# sumo1.net
KiCad netlist of a schematic drawn in EAGLE
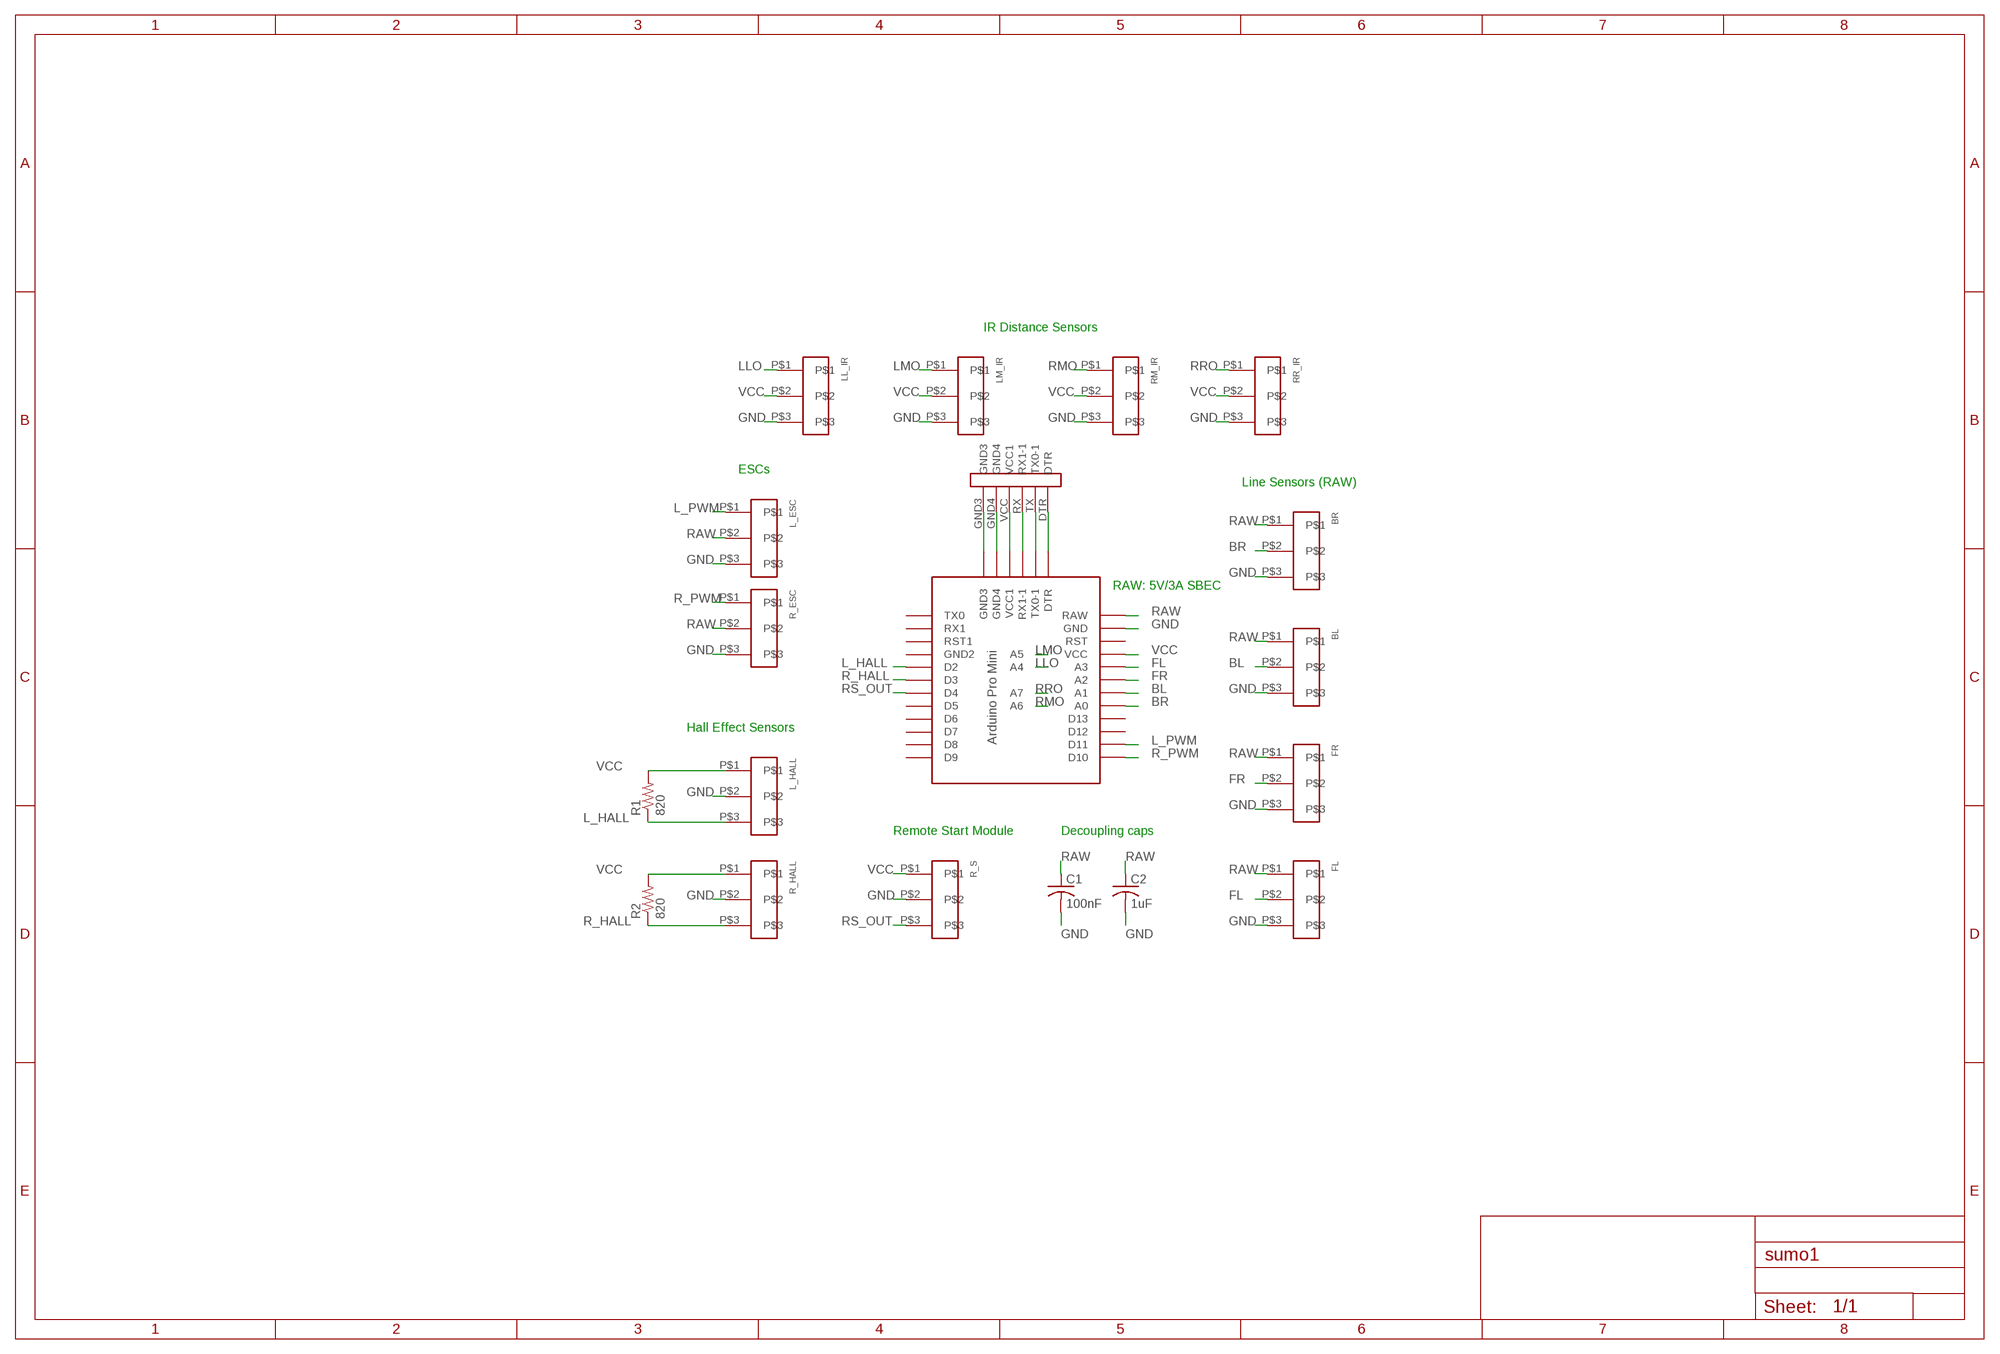
[diagram p0: schematic, sheet 1]

(export (version "E")
  (design (tool "Eeschema 10.0.6"))
  (components
    (comp (ref "BL")
      (value "PHOENIX_CONTACT_3PIN")
      (footprint "eagle-import:PHOENIX_CONTACT_3PIN")
      (libsource (lib "eagle-import") (part "PHOENIX_CONTACT_3PIN"))
    )
    (comp (ref "BR")
      (value "PHOENIX_CONTACT_3PIN")
      (footprint "eagle-import:PHOENIX_CONTACT_3PIN")
      (libsource (lib "eagle-import") (part "PHOENIX_CONTACT_3PIN"))
    )
    (comp (ref "C1")
      (value "100nF")
      (footprint "eagle-import:C0603")
      (libsource (lib "eagle-import") (part "C-USC0603"))
    )
    (comp (ref "C2")
      (value "1uF")
      (footprint "eagle-import:C0603")
      (libsource (lib "eagle-import") (part "C-USC0603"))
    )
    (comp (ref "FL")
      (value "PHOENIX_CONTACT_3PIN")
      (footprint "eagle-import:PHOENIX_CONTACT_3PIN")
      (libsource (lib "eagle-import") (part "PHOENIX_CONTACT_3PIN"))
    )
    (comp (ref "FR")
      (value "PHOENIX_CONTACT_3PIN")
      (footprint "eagle-import:PHOENIX_CONTACT_3PIN")
      (libsource (lib "eagle-import") (part "PHOENIX_CONTACT_3PIN"))
    )
    (comp (ref "LL_IR")
      (value "PHOENIX_CONTACT_3PIN")
      (footprint "eagle-import:PHOENIX_CONTACT_3PIN")
      (libsource (lib "eagle-import") (part "PHOENIX_CONTACT_3PIN"))
    )
    (comp (ref "LM_IR")
      (value "PHOENIX_CONTACT_3PIN")
      (footprint "eagle-import:PHOENIX_CONTACT_3PIN")
      (libsource (lib "eagle-import") (part "PHOENIX_CONTACT_3PIN"))
    )
    (comp (ref "L_ESC")
      (value "PHOENIX_CONTACT_3PIN")
      (footprint "eagle-import:PHOENIX_CONTACT_3PIN")
      (libsource (lib "eagle-import") (part "PHOENIX_CONTACT_3PIN"))
    )
    (comp (ref "L_HALL")
      (value "PHOENIX_CONTACT_3PIN")
      (footprint "eagle-import:PHOENIX_CONTACT_3PIN")
      (libsource (lib "eagle-import") (part "PHOENIX_CONTACT_3PIN"))
    )
    (comp (ref "R1")
      (value "820")
      (footprint "eagle-import:R0603")
      (libsource (lib "eagle-import") (part "R-US_R0603"))
    )
    (comp (ref "R2")
      (value "820")
      (footprint "eagle-import:R0603")
      (libsource (lib "eagle-import") (part "R-US_R0603"))
    )
    (comp (ref "RM_IR")
      (value "PHOENIX_CONTACT_3PIN")
      (footprint "eagle-import:PHOENIX_CONTACT_3PIN")
      (libsource (lib "eagle-import") (part "PHOENIX_CONTACT_3PIN"))
    )
    (comp (ref "RR_IR")
      (value "PHOENIX_CONTACT_3PIN")
      (footprint "eagle-import:PHOENIX_CONTACT_3PIN")
      (libsource (lib "eagle-import") (part "PHOENIX_CONTACT_3PIN"))
    )
    (comp (ref "R_ESC")
      (value "PHOENIX_CONTACT_3PIN")
      (footprint "eagle-import:PHOENIX_CONTACT_3PIN")
      (libsource (lib "eagle-import") (part "PHOENIX_CONTACT_3PIN"))
    )
    (comp (ref "R_HALL")
      (value "PHOENIX_CONTACT_3PIN")
      (footprint "eagle-import:PHOENIX_CONTACT_3PIN")
      (libsource (lib "eagle-import") (part "PHOENIX_CONTACT_3PIN"))
    )
    (comp (ref "R_S")
      (value "PHOENIX_CONTACT_3PIN")
      (footprint "eagle-import:PHOENIX_CONTACT_3PIN")
      (libsource (lib "eagle-import") (part "PHOENIX_CONTACT_3PIN"))
    )
    (comp (ref "U$1")
      (value "PRO-MINI-2")
      (footprint "eagle-import:PRO-MINI-2")
      (libsource (lib "eagle-import") (part "PRO-MINI-2"))
    )
    (comp (ref "U$2")
      (value "6-PIN")
      (footprint "eagle-import:6-PIN")
      (libsource (lib "eagle-import") (part "6-PIN"))
    )
  )
  (nets
    (net (code "1") (name "/BL") (class "Default")
      (node (ref "BL") (pin "P$2") (pinfunction "P$2_P$2") (pintype "bidirectional"))
      (node (ref "U$1") (pin "A1") (pinfunction "A1_A1") (pintype "bidirectional"))
    )
    (net (code "2") (name "/BR") (class "Default")
      (node (ref "BR") (pin "P$2") (pinfunction "P$2_P$2") (pintype "bidirectional"))
      (node (ref "U$1") (pin "A0") (pinfunction "A0_A0") (pintype "bidirectional"))
    )
    (net (code "3") (name "/FL") (class "Default")
      (node (ref "FL") (pin "P$2") (pinfunction "P$2_P$2") (pintype "bidirectional"))
      (node (ref "U$1") (pin "A3") (pinfunction "A3_A3") (pintype "bidirectional"))
    )
    (net (code "4") (name "/FR") (class "Default")
      (node (ref "FR") (pin "P$2") (pinfunction "P$2_P$2") (pintype "bidirectional"))
      (node (ref "U$1") (pin "A2") (pinfunction "A2_A2") (pintype "bidirectional"))
    )
    (net (code "5") (name "/GND") (class "Default")
      (node (ref "BL") (pin "P$3") (pinfunction "P$3_P$3") (pintype "bidirectional"))
      (node (ref "BR") (pin "P$3") (pinfunction "P$3_P$3") (pintype "bidirectional"))
      (node (ref "C1") (pin "2") (pinfunction "2_2") (pintype "passive"))
      (node (ref "C2") (pin "2") (pinfunction "2_2") (pintype "passive"))
      (node (ref "FL") (pin "P$3") (pinfunction "P$3_P$3") (pintype "bidirectional"))
      (node (ref "FR") (pin "P$3") (pinfunction "P$3_P$3") (pintype "bidirectional"))
      (node (ref "LL_IR") (pin "P$3") (pinfunction "P$3_P$3") (pintype "bidirectional"))
      (node (ref "LM_IR") (pin "P$3") (pinfunction "P$3_P$3") (pintype "bidirectional"))
      (node (ref "L_ESC") (pin "P$3") (pinfunction "P$3_P$3") (pintype "bidirectional"))
      (node (ref "L_HALL") (pin "P$2") (pinfunction "P$2_P$2") (pintype "bidirectional"))
      (node (ref "RM_IR") (pin "P$3") (pinfunction "P$3_P$3") (pintype "bidirectional"))
      (node (ref "RR_IR") (pin "P$3") (pinfunction "P$3_P$3") (pintype "bidirectional"))
      (node (ref "R_ESC") (pin "P$3") (pinfunction "P$3_P$3") (pintype "bidirectional"))
      (node (ref "R_HALL") (pin "P$2") (pinfunction "P$2_P$2") (pintype "bidirectional"))
      (node (ref "R_S") (pin "P$2") (pinfunction "P$2_P$2") (pintype "bidirectional"))
      (node (ref "U$1") (pin "GND") (pinfunction "GND_GND") (pintype "bidirectional"))
    )
    (net (code "6") (name "/LLO") (class "Default")
      (node (ref "LL_IR") (pin "P$1") (pinfunction "P$1_P$1") (pintype "bidirectional"))
      (node (ref "U$1") (pin "A4") (pinfunction "A4_A4") (pintype "bidirectional"))
    )
    (net (code "7") (name "/LMO") (class "Default")
      (node (ref "LM_IR") (pin "P$1") (pinfunction "P$1_P$1") (pintype "bidirectional"))
      (node (ref "U$1") (pin "A5") (pinfunction "A5_A5") (pintype "bidirectional"))
    )
    (net (code "8") (name "/L_HALL") (class "Default")
      (node (ref "L_HALL") (pin "P$3") (pinfunction "P$3_P$3") (pintype "bidirectional"))
      (node (ref "R1") (pin "1") (pinfunction "1_1") (pintype "passive"))
      (node (ref "U$1") (pin "D2") (pinfunction "D2_D2") (pintype "bidirectional"))
    )
    (net (code "9") (name "/L_PWM") (class "Default")
      (node (ref "L_ESC") (pin "P$1") (pinfunction "P$1_P$1") (pintype "bidirectional"))
      (node (ref "U$1") (pin "D11") (pinfunction "D11_D11") (pintype "bidirectional"))
    )
    (net (code "10") (name "/RAW") (class "Default")
      (node (ref "BL") (pin "P$1") (pinfunction "P$1_P$1") (pintype "bidirectional"))
      (node (ref "BR") (pin "P$1") (pinfunction "P$1_P$1") (pintype "bidirectional"))
      (node (ref "C1") (pin "1") (pinfunction "1_1") (pintype "passive"))
      (node (ref "C2") (pin "1") (pinfunction "1_1") (pintype "passive"))
      (node (ref "FL") (pin "P$1") (pinfunction "P$1_P$1") (pintype "bidirectional"))
      (node (ref "FR") (pin "P$1") (pinfunction "P$1_P$1") (pintype "bidirectional"))
      (node (ref "L_ESC") (pin "P$2") (pinfunction "P$2_P$2") (pintype "bidirectional"))
      (node (ref "R_ESC") (pin "P$2") (pinfunction "P$2_P$2") (pintype "bidirectional"))
      (node (ref "U$1") (pin "RAW") (pinfunction "RAW_RAW") (pintype "bidirectional"))
    )
    (net (code "11") (name "/RMO") (class "Default")
      (node (ref "RM_IR") (pin "P$1") (pinfunction "P$1_P$1") (pintype "bidirectional"))
      (node (ref "U$1") (pin "A6") (pinfunction "A6_A6") (pintype "bidirectional"))
    )
    (net (code "12") (name "/RRO") (class "Default")
      (node (ref "RR_IR") (pin "P$1") (pinfunction "P$1_P$1") (pintype "bidirectional"))
      (node (ref "U$1") (pin "A7") (pinfunction "A7_A7") (pintype "bidirectional"))
    )
    (net (code "13") (name "/RS_OUT") (class "Default")
      (node (ref "R_S") (pin "P$3") (pinfunction "P$3_P$3") (pintype "bidirectional"))
      (node (ref "U$1") (pin "D4") (pinfunction "D4_D4") (pintype "bidirectional"))
    )
    (net (code "14") (name "/R_HALL") (class "Default")
      (node (ref "R2") (pin "1") (pinfunction "1_1") (pintype "passive"))
      (node (ref "R_HALL") (pin "P$3") (pinfunction "P$3_P$3") (pintype "bidirectional"))
      (node (ref "U$1") (pin "D3") (pinfunction "D3_D3") (pintype "bidirectional"))
    )
    (net (code "15") (name "/R_PWM") (class "Default")
      (node (ref "R_ESC") (pin "P$1") (pinfunction "P$1_P$1") (pintype "bidirectional"))
      (node (ref "U$1") (pin "D10") (pinfunction "D10_D10") (pintype "bidirectional"))
    )
    (net (code "16") (name "/VCC") (class "Default")
      (node (ref "LL_IR") (pin "P$2") (pinfunction "P$2_P$2") (pintype "bidirectional"))
      (node (ref "LM_IR") (pin "P$2") (pinfunction "P$2_P$2") (pintype "bidirectional"))
      (node (ref "L_HALL") (pin "P$1") (pinfunction "P$1_P$1") (pintype "bidirectional"))
      (node (ref "R1") (pin "2") (pinfunction "2_2") (pintype "passive"))
      (node (ref "R2") (pin "2") (pinfunction "2_2") (pintype "passive"))
      (node (ref "RM_IR") (pin "P$2") (pinfunction "P$2_P$2") (pintype "bidirectional"))
      (node (ref "RR_IR") (pin "P$2") (pinfunction "P$2_P$2") (pintype "bidirectional"))
      (node (ref "R_HALL") (pin "P$1") (pinfunction "P$1_P$1") (pintype "bidirectional"))
      (node (ref "R_S") (pin "P$1") (pinfunction "P$1_P$1") (pintype "bidirectional"))
      (node (ref "U$1") (pin "VCC") (pinfunction "VCC_VCC") (pintype "bidirectional"))
    )
    (net (code "17") (name "Net-(U$1-GND3)") (class "Default")
      (node (ref "U$1") (pin "GND2") (pinfunction "GND3_GND2") (pintype "bidirectional"))
      (node (ref "U$2") (pin "GND3") (pinfunction "GND3_GND3") (pintype "bidirectional"))
    )
    (net (code "18") (name "Net-(U$1-GND4)") (class "Default")
      (node (ref "U$1") (pin "GND3") (pinfunction "GND4_GND3") (pintype "bidirectional"))
      (node (ref "U$2") (pin "GND4") (pinfunction "GND4_GND4") (pintype "bidirectional"))
    )
    (net (code "19") (name "Net-(U$1-PadDTR)") (class "Default")
      (node (ref "U$1") (pin "DTR") (pinfunction "DTR_DTR") (pintype "bidirectional"))
      (node (ref "U$2") (pin "DTR") (pinfunction "DTR_DTR") (pintype "bidirectional"))
    )
    (net (code "20") (name "Net-(U$2-RX1-1)") (class "Default")
      (node (ref "U$1") (pin "RX1-1") (pinfunction "RX1-1_RX1-1") (pintype "bidirectional"))
      (node (ref "U$2") (pin "RX") (pinfunction "RX1-1_RX") (pintype "bidirectional"))
    )
    (net (code "21") (name "Net-(U$2-TX0-1)") (class "Default")
      (node (ref "U$1") (pin "TX0-1") (pinfunction "TX0-1_TX0-1") (pintype "bidirectional"))
      (node (ref "U$2") (pin "TX") (pinfunction "TX0-1_TX") (pintype "bidirectional"))
    )
    (net (code "22") (name "Net-(U$2-VCC1)") (class "Default")
      (node (ref "U$1") (pin "VCC1") (pinfunction "VCC1_VCC1") (pintype "bidirectional"))
      (node (ref "U$2") (pin "VCC") (pinfunction "VCC1_VCC") (pintype "bidirectional"))
    )
    (net (code "23") (name "unconnected-(U$1-GND2-PadGND1)") (class "Default")
      (node (ref "U$1") (pin "GND1") (pinfunction "GND2_GND1") (pintype "bidirectional"))
    )
    (net (code "24") (name "unconnected-(U$1-PadD5)") (class "Default")
      (node (ref "U$1") (pin "D5") (pinfunction "D5_D5") (pintype "bidirectional"))
    )
    (net (code "25") (name "unconnected-(U$1-PadD6)") (class "Default")
      (node (ref "U$1") (pin "D6") (pinfunction "D6_D6") (pintype "bidirectional"))
    )
    (net (code "26") (name "unconnected-(U$1-PadD7)") (class "Default")
      (node (ref "U$1") (pin "D7") (pinfunction "D7_D7") (pintype "bidirectional"))
    )
    (net (code "27") (name "unconnected-(U$1-PadD8)") (class "Default")
      (node (ref "U$1") (pin "D8") (pinfunction "D8_D8") (pintype "bidirectional"))
    )
    (net (code "28") (name "unconnected-(U$1-PadD9)") (class "Default")
      (node (ref "U$1") (pin "D9") (pinfunction "D9_D9") (pintype "bidirectional"))
    )
    (net (code "29") (name "unconnected-(U$1-PadD12)") (class "Default")
      (node (ref "U$1") (pin "D12") (pinfunction "D12_D12") (pintype "bidirectional"))
    )
    (net (code "30") (name "unconnected-(U$1-PadD13)") (class "Default")
      (node (ref "U$1") (pin "D13") (pinfunction "D13_D13") (pintype "bidirectional"))
    )
    (net (code "31") (name "unconnected-(U$1-PadRST)") (class "Default")
      (node (ref "U$1") (pin "RST") (pinfunction "RST_RST") (pintype "bidirectional"))
    )
    (net (code "32") (name "unconnected-(U$1-PadRST1)") (class "Default")
      (node (ref "U$1") (pin "RST1") (pinfunction "RST1_RST1") (pintype "bidirectional"))
    )
    (net (code "33") (name "unconnected-(U$1-PadRX1)") (class "Default")
      (node (ref "U$1") (pin "RX1") (pinfunction "RX1_RX1") (pintype "bidirectional"))
    )
    (net (code "34") (name "unconnected-(U$1-PadTX0)") (class "Default")
      (node (ref "U$1") (pin "TX0") (pinfunction "TX0_TX0") (pintype "bidirectional"))
    )
  )
)
